# stereomix-back.net
KiCad netlist of a schematic drawn in EAGLE
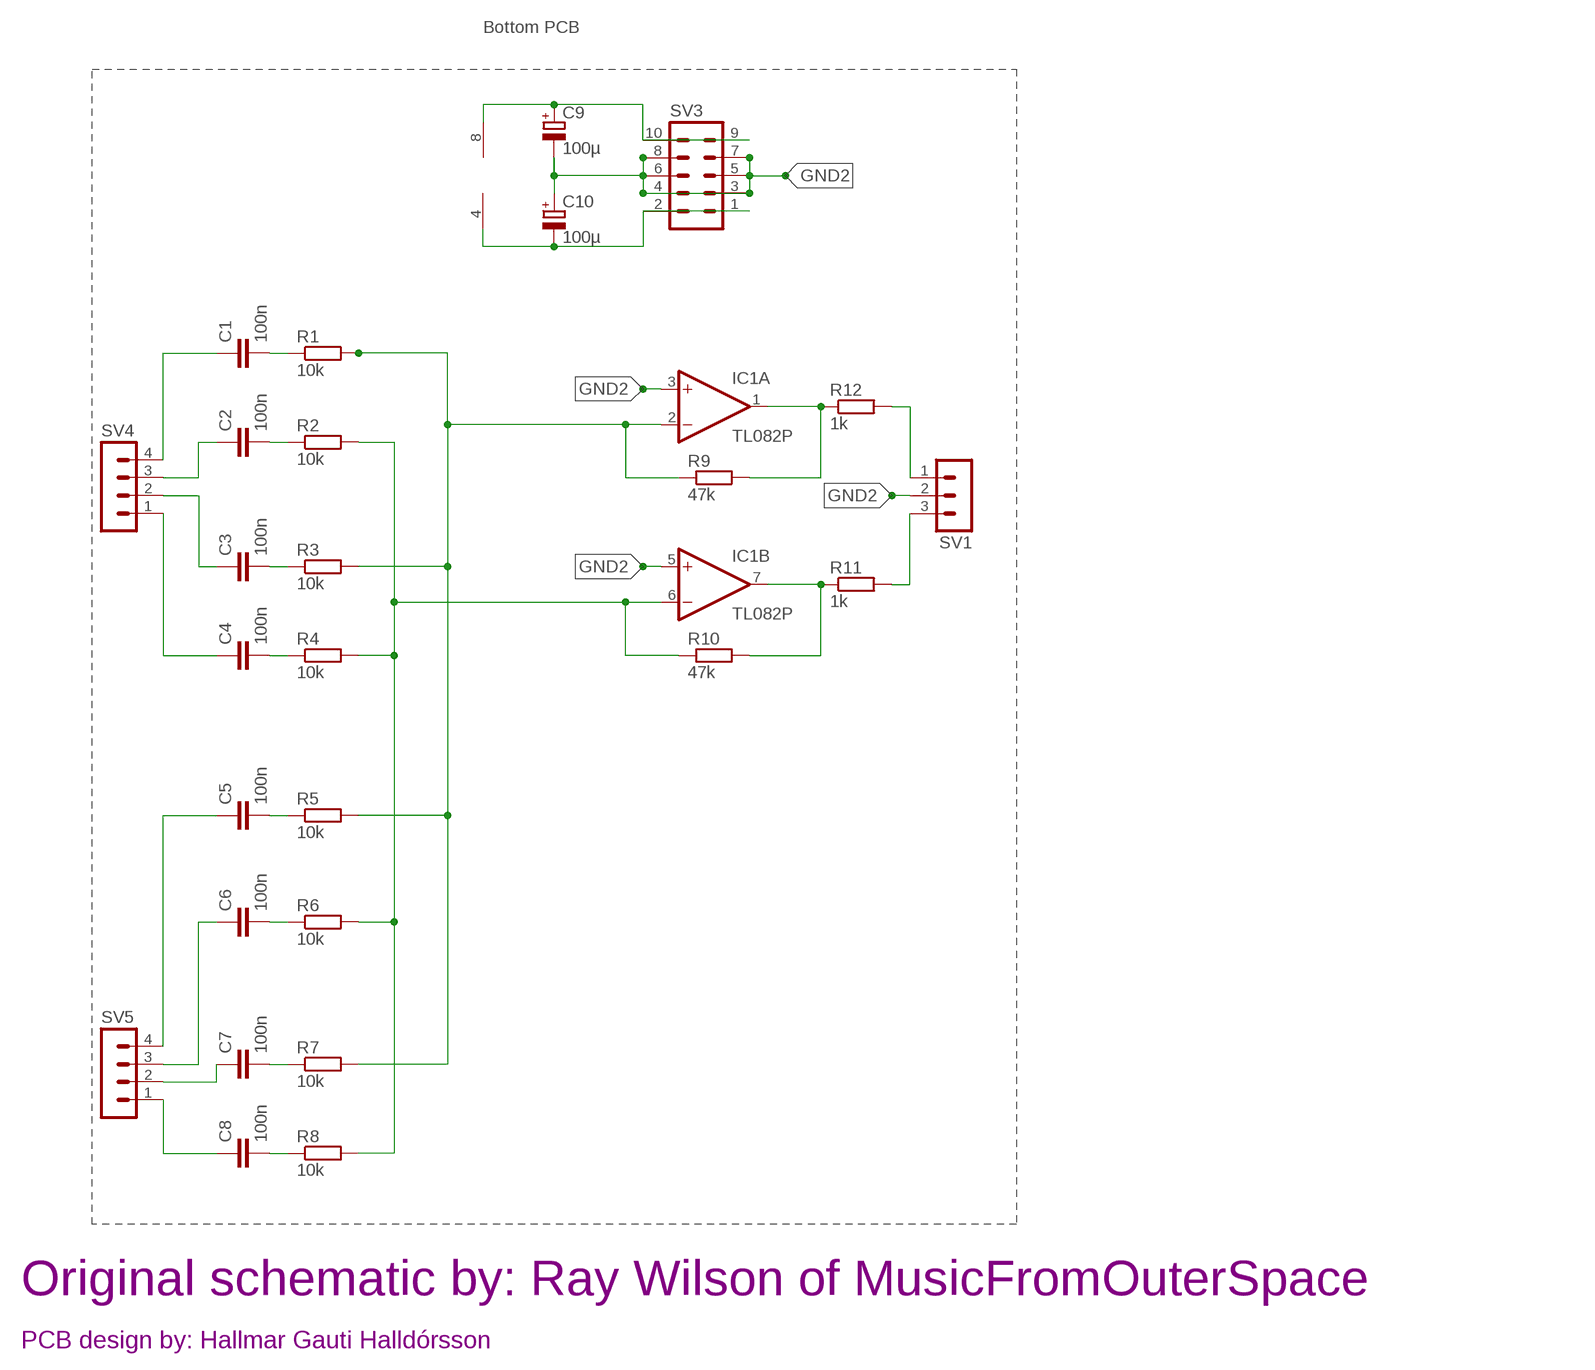
[diagram p0: schematic, sheet 1]

(export (version "E")
  (design (tool "Eeschema 10.0.6"))
  (components
    (comp (ref "C1")
      (value "100n")
      (footprint "eagle-import:C050-024X044")
      (libsource (lib "eagle-import") (part "C-EU050-024X044"))
    )
    (comp (ref "C2")
      (value "100n")
      (footprint "eagle-import:C050-024X044")
      (libsource (lib "eagle-import") (part "C-EU050-024X044"))
    )
    (comp (ref "C3")
      (value "100n")
      (footprint "eagle-import:C050-024X044")
      (libsource (lib "eagle-import") (part "C-EU050-024X044"))
    )
    (comp (ref "C4")
      (value "100n")
      (footprint "eagle-import:C050-024X044")
      (libsource (lib "eagle-import") (part "C-EU050-024X044"))
    )
    (comp (ref "C5")
      (value "100n")
      (footprint "eagle-import:C050-024X044")
      (libsource (lib "eagle-import") (part "C-EU050-024X044"))
    )
    (comp (ref "C6")
      (value "100n")
      (footprint "eagle-import:C050-024X044")
      (libsource (lib "eagle-import") (part "C-EU050-024X044"))
    )
    (comp (ref "C7")
      (value "100n")
      (footprint "eagle-import:C050-024X044")
      (libsource (lib "eagle-import") (part "C-EU050-024X044"))
    )
    (comp (ref "C8")
      (value "100n")
      (footprint "eagle-import:C050-024X044")
      (libsource (lib "eagle-import") (part "C-EU050-024X044"))
    )
    (comp (ref "C9")
      (value "100µ")
      (footprint "eagle-import:E2,5-6")
      (libsource (lib "eagle-import") (part "CPOL-EUE2.5-6"))
    )
    (comp (ref "C10")
      (value "100µ")
      (footprint "eagle-import:E2,5-6E")
      (libsource (lib "eagle-import") (part "CPOL-EUE2,5-6E"))
    )
    (comp (ref "IC1")
      (value "TL082P")
      (footprint "eagle-import:DIL08")
      (libsource (lib "eagle-import") (part "TL082P"))
    )
    (comp (ref "R1")
      (value "10k")
      (footprint "eagle-import:0204_7")
      (libsource (lib "eagle-import") (part "R-EU_0204/7"))
    )
    (comp (ref "R2")
      (value "10k")
      (footprint "eagle-import:0204_7")
      (libsource (lib "eagle-import") (part "R-EU_0204/7"))
    )
    (comp (ref "R3")
      (value "10k")
      (footprint "eagle-import:0204_7")
      (libsource (lib "eagle-import") (part "R-EU_0204/7"))
    )
    (comp (ref "R4")
      (value "10k")
      (footprint "eagle-import:0204_7")
      (libsource (lib "eagle-import") (part "R-EU_0204/7"))
    )
    (comp (ref "R5")
      (value "10k")
      (footprint "eagle-import:0204_7")
      (libsource (lib "eagle-import") (part "R-EU_0204/7"))
    )
    (comp (ref "R6")
      (value "10k")
      (footprint "eagle-import:0204_7")
      (libsource (lib "eagle-import") (part "R-EU_0204/7"))
    )
    (comp (ref "R7")
      (value "10k")
      (footprint "eagle-import:0204_7")
      (libsource (lib "eagle-import") (part "R-EU_0204/7"))
    )
    (comp (ref "R8")
      (value "10k")
      (footprint "eagle-import:0204_7")
      (libsource (lib "eagle-import") (part "R-EU_0204/7"))
    )
    (comp (ref "R9")
      (value "47k")
      (footprint "eagle-import:0204_7")
      (libsource (lib "eagle-import") (part "R-EU_0204/7"))
    )
    (comp (ref "R10")
      (value "47k")
      (footprint "eagle-import:0204_7")
      (libsource (lib "eagle-import") (part "R-EU_0204/7"))
    )
    (comp (ref "R11")
      (value "1k")
      (footprint "eagle-import:0204_7")
      (libsource (lib "eagle-import") (part "R-EU_0204/7"))
    )
    (comp (ref "R12")
      (value "1k")
      (footprint "eagle-import:0204_7")
      (libsource (lib "eagle-import") (part "R-EU_0204/7"))
    )
    (comp (ref "SV1")
      (value "MA03-1")
      (footprint "eagle-import:MA03-1")
      (libsource (lib "eagle-import") (part "MA03-1"))
    )
    (comp (ref "SV3")
      (value "MA05-2")
      (footprint "eagle-import:MA05-2")
      (libsource (lib "eagle-import") (part "MA05-2"))
    )
    (comp (ref "SV4")
      (value "MA04-1")
      (footprint "eagle-import:MA04-1")
      (libsource (lib "eagle-import") (part "MA04-1"))
    )
    (comp (ref "SV5")
      (value "MA04-1")
      (footprint "eagle-import:MA04-1")
      (libsource (lib "eagle-import") (part "MA04-1"))
    )
  )
  (nets
    (net (code "1") (name "GND2") (class "Default")
      (node (ref "C10") (pin "+") (pinfunction "+_+") (pintype "passive"))
      (node (ref "C9") (pin "-") (pinfunction "-_-") (pintype "passive"))
      (node (ref "IC1") (pin "3") (pinfunction "+IN_3") (pintype "input"))
      (node (ref "IC1") (pin "5") (pinfunction "+IN_5") (pintype "input"))
      (node (ref "SV1") (pin "2") (pinfunction "2_2") (pintype "passive"))
      (node (ref "SV3") (pin "3") (pinfunction "3_3") (pintype "passive"))
      (node (ref "SV3") (pin "4") (pinfunction "4_4") (pintype "passive"))
      (node (ref "SV3") (pin "5") (pinfunction "5_5") (pintype "passive"))
      (node (ref "SV3") (pin "6") (pinfunction "6_6") (pintype "passive"))
      (node (ref "SV3") (pin "7") (pinfunction "7_7") (pintype "passive"))
      (node (ref "SV3") (pin "8") (pinfunction "8_8") (pintype "passive"))
    )
    (net (code "2") (name "Net-(C1-Pad1)") (class "Default")
      (node (ref "C1") (pin "1") (pinfunction "1_1") (pintype "passive"))
      (node (ref "SV4") (pin "4") (pinfunction "4_4") (pintype "passive"))
    )
    (net (code "3") (name "Net-(C1-Pad2)") (class "Default")
      (node (ref "C1") (pin "2") (pinfunction "2_2") (pintype "passive"))
      (node (ref "R1") (pin "1") (pinfunction "1_1") (pintype "passive"))
    )
    (net (code "4") (name "Net-(C2-Pad1)") (class "Default")
      (node (ref "C2") (pin "1") (pinfunction "1_1") (pintype "passive"))
      (node (ref "SV4") (pin "3") (pinfunction "3_3") (pintype "passive"))
    )
    (net (code "5") (name "Net-(C2-Pad2)") (class "Default")
      (node (ref "C2") (pin "2") (pinfunction "2_2") (pintype "passive"))
      (node (ref "R2") (pin "1") (pinfunction "1_1") (pintype "passive"))
    )
    (net (code "6") (name "Net-(C3-Pad1)") (class "Default")
      (node (ref "C3") (pin "1") (pinfunction "1_1") (pintype "passive"))
      (node (ref "SV4") (pin "2") (pinfunction "2_2") (pintype "passive"))
    )
    (net (code "7") (name "Net-(C3-Pad2)") (class "Default")
      (node (ref "C3") (pin "2") (pinfunction "2_2") (pintype "passive"))
      (node (ref "R3") (pin "1") (pinfunction "1_1") (pintype "passive"))
    )
    (net (code "8") (name "Net-(C4-Pad1)") (class "Default")
      (node (ref "C4") (pin "1") (pinfunction "1_1") (pintype "passive"))
      (node (ref "SV4") (pin "1") (pinfunction "1_1") (pintype "passive"))
    )
    (net (code "9") (name "Net-(C4-Pad2)") (class "Default")
      (node (ref "C4") (pin "2") (pinfunction "2_2") (pintype "passive"))
      (node (ref "R4") (pin "1") (pinfunction "1_1") (pintype "passive"))
    )
    (net (code "10") (name "Net-(C5-Pad1)") (class "Default")
      (node (ref "C5") (pin "1") (pinfunction "1_1") (pintype "passive"))
      (node (ref "SV5") (pin "4") (pinfunction "4_4") (pintype "passive"))
    )
    (net (code "11") (name "Net-(C5-Pad2)") (class "Default")
      (node (ref "C5") (pin "2") (pinfunction "2_2") (pintype "passive"))
      (node (ref "R5") (pin "1") (pinfunction "1_1") (pintype "passive"))
    )
    (net (code "12") (name "Net-(C6-Pad1)") (class "Default")
      (node (ref "C6") (pin "1") (pinfunction "1_1") (pintype "passive"))
      (node (ref "SV5") (pin "3") (pinfunction "3_3") (pintype "passive"))
    )
    (net (code "13") (name "Net-(C6-Pad2)") (class "Default")
      (node (ref "C6") (pin "2") (pinfunction "2_2") (pintype "passive"))
      (node (ref "R6") (pin "1") (pinfunction "1_1") (pintype "passive"))
    )
    (net (code "14") (name "Net-(C7-Pad1)") (class "Default")
      (node (ref "C7") (pin "1") (pinfunction "1_1") (pintype "passive"))
      (node (ref "SV5") (pin "2") (pinfunction "2_2") (pintype "passive"))
    )
    (net (code "15") (name "Net-(C7-Pad2)") (class "Default")
      (node (ref "C7") (pin "2") (pinfunction "2_2") (pintype "passive"))
      (node (ref "R7") (pin "1") (pinfunction "1_1") (pintype "passive"))
    )
    (net (code "16") (name "Net-(C8-Pad1)") (class "Default")
      (node (ref "C8") (pin "1") (pinfunction "1_1") (pintype "passive"))
      (node (ref "SV5") (pin "1") (pinfunction "1_1") (pintype "passive"))
    )
    (net (code "17") (name "Net-(C8-Pad2)") (class "Default")
      (node (ref "C8") (pin "2") (pinfunction "2_2") (pintype "passive"))
      (node (ref "R8") (pin "1") (pinfunction "1_1") (pintype "passive"))
    )
    (net (code "18") (name "Net-(IC1A--IN)") (class "Default")
      (node (ref "IC1") (pin "2") (pinfunction "-IN_2") (pintype "input"))
      (node (ref "R1") (pin "2") (pinfunction "2_2") (pintype "passive"))
      (node (ref "R3") (pin "2") (pinfunction "2_2") (pintype "passive"))
      (node (ref "R5") (pin "2") (pinfunction "2_2") (pintype "passive"))
      (node (ref "R7") (pin "2") (pinfunction "2_2") (pintype "passive"))
      (node (ref "R9") (pin "1") (pinfunction "1_1") (pintype "passive"))
    )
    (net (code "19") (name "Net-(IC1A-OUT)") (class "Default")
      (node (ref "IC1") (pin "1") (pinfunction "OUT_1") (pintype "output"))
      (node (ref "R12") (pin "1") (pinfunction "1_1") (pintype "passive"))
      (node (ref "R9") (pin "2") (pinfunction "2_2") (pintype "passive"))
    )
    (net (code "20") (name "Net-(IC1B--IN)") (class "Default")
      (node (ref "IC1") (pin "6") (pinfunction "-IN_6") (pintype "input"))
      (node (ref "R10") (pin "1") (pinfunction "1_1") (pintype "passive"))
      (node (ref "R2") (pin "2") (pinfunction "2_2") (pintype "passive"))
      (node (ref "R4") (pin "2") (pinfunction "2_2") (pintype "passive"))
      (node (ref "R6") (pin "2") (pinfunction "2_2") (pintype "passive"))
      (node (ref "R8") (pin "2") (pinfunction "2_2") (pintype "passive"))
    )
    (net (code "21") (name "Net-(IC1B-OUT)") (class "Default")
      (node (ref "IC1") (pin "7") (pinfunction "OUT_7") (pintype "output"))
      (node (ref "R10") (pin "2") (pinfunction "2_2") (pintype "passive"))
      (node (ref "R11") (pin "1") (pinfunction "1_1") (pintype "passive"))
    )
    (net (code "22") (name "Net-(IC1C-V+)") (class "Default")
      (node (ref "C9") (pin "+") (pinfunction "+_+") (pintype "passive"))
      (node (ref "IC1") (pin "8") (pinfunction "V+_8") (pintype "power_in"))
      (node (ref "SV3") (pin "10") (pinfunction "10_10") (pintype "passive"))
      (node (ref "SV3") (pin "9") (pinfunction "9_9") (pintype "passive"))
    )
    (net (code "23") (name "Net-(IC1C-V-)") (class "Default")
      (node (ref "C10") (pin "-") (pinfunction "-_-") (pintype "passive"))
      (node (ref "IC1") (pin "4") (pinfunction "V-_4") (pintype "power_in"))
      (node (ref "SV3") (pin "1") (pinfunction "1_1") (pintype "passive"))
      (node (ref "SV3") (pin "2") (pinfunction "2_2") (pintype "passive"))
    )
    (net (code "24") (name "Net-(R11-Pad2)") (class "Default")
      (node (ref "R11") (pin "2") (pinfunction "2_2") (pintype "passive"))
      (node (ref "SV1") (pin "3") (pinfunction "3_3") (pintype "passive"))
    )
    (net (code "25") (name "Net-(R12-Pad2)") (class "Default")
      (node (ref "R12") (pin "2") (pinfunction "2_2") (pintype "passive"))
      (node (ref "SV1") (pin "1") (pinfunction "1_1") (pintype "passive"))
    )
  )
)
